# LDR_Sensor_SCH.net
KiCad netlist of a schematic drawn in Altium Designer
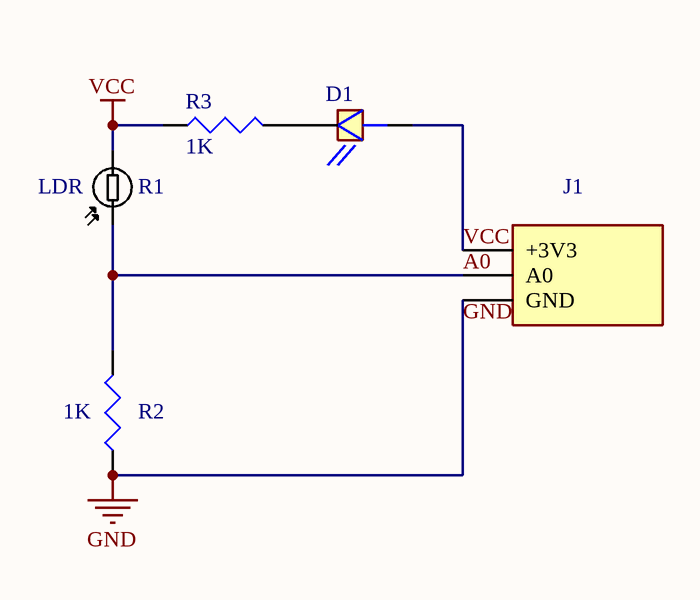
[diagram p0: LDR_Sensor_SCH.SchDoc]

(export (version "E")
  (design (tool "Eeschema 10.0.6"))
  (components
    (comp (ref "D1")
      (value "OVLAW4CB7")
      (footprint "LEDRD254W50D305H520P")
      (description "Ovlaw4Cb7 White LED 3mm (T-1) Round Lens Through Hole Package ¦ Optek (TT Electronics) OVLAW4CB7")
      (fields (field (name "MF") "TT Electronics/Optek"))
      (libsource (lib "LDR_Sensor_SCHLib") (part "OVLAW4CB7"))
    )
    (comp (ref "J1")
      (value "MTSW-103-07-G-S-140")
      (footprint "PBC03SAAN")
      (libsource (lib "LDR_Sensor_SCHLib") (part "MTSW-103-07-G-S-140"))
    )
    (comp (ref "R1")
      (value "LDR")
      (footprint "PDV-P8104")
      (description "CDS PHOTORESISTOR 5MM")
      (fields
        (field (name "MANUFACTURER") "Advanced Photonix")
        (field (name "MANUFACTURER PART NUMBER") "PDV-P8104")
      )
      (libsource (lib "LDR_Sensor_SCHLib") (part "PDV-P8104"))
    )
    (comp (ref "R2")
      (value "1K")
      (footprint "CF14JT1K00")
      (description "RES 1K OHM 5% 1/4W AXIAL")
      (fields
        (field (name "MANUFACTURER") "Stackpole Electronics")
        (field (name "MANUFACTURER PART NUMBER") "CF14JT1K00")
      )
      (libsource (lib "LDR_Sensor_SCHLib") (part "CF14JT1K00"))
    )
    (comp (ref "R3")
      (value "1K")
      (footprint "CF14JT1K00")
      (description "RES 1K OHM 5% 1/4W AXIAL")
      (fields
        (field (name "MANUFACTURER") "Stackpole Electronics")
        (field (name "MANUFACTURER PART NUMBER") "CF14JT1K00")
      )
      (libsource (lib "LDR_Sensor_SCHLib") (part "CF14JT1K00"))
    )
  )
  (nets
    (net (code "1") (name "/A0") (class "Default")
      (node (ref "J1") (pin "02") (pinfunction "A0_02") (pintype "passive"))
      (node (ref "R1") (pin "2") (pinfunction "2_2") (pintype "passive"))
      (node (ref "R2") (pin "2") (pinfunction "2_2") (pintype "passive"))
    )
    (net (code "2") (name "GND") (class "Default")
      (node (ref "J1") (pin "03") (pinfunction "GND_03") (pintype "passive"))
      (node (ref "R2") (pin "1") (pinfunction "1_1") (pintype "passive"))
    )
    (net (code "3") (name "Net-(D1-PadC)") (class "Default")
      (node (ref "D1") (pin "C") (pinfunction "C_C") (pintype "passive"))
      (node (ref "R3") (pin "2") (pinfunction "2_2") (pintype "passive"))
    )
    (net (code "4") (name "VCC") (class "Default")
      (node (ref "D1") (pin "A") (pinfunction "A_A") (pintype "passive"))
      (node (ref "J1") (pin "VCC") (pinfunction "+3V3_VCC") (pintype "passive"))
      (node (ref "R1") (pin "1") (pinfunction "1_1") (pintype "passive"))
      (node (ref "R3") (pin "1") (pinfunction "1_1") (pintype "passive"))
    )
  )
)
